# DCDC_stepdown.net
KiCad netlist of a schematic drawn in Altium Designer
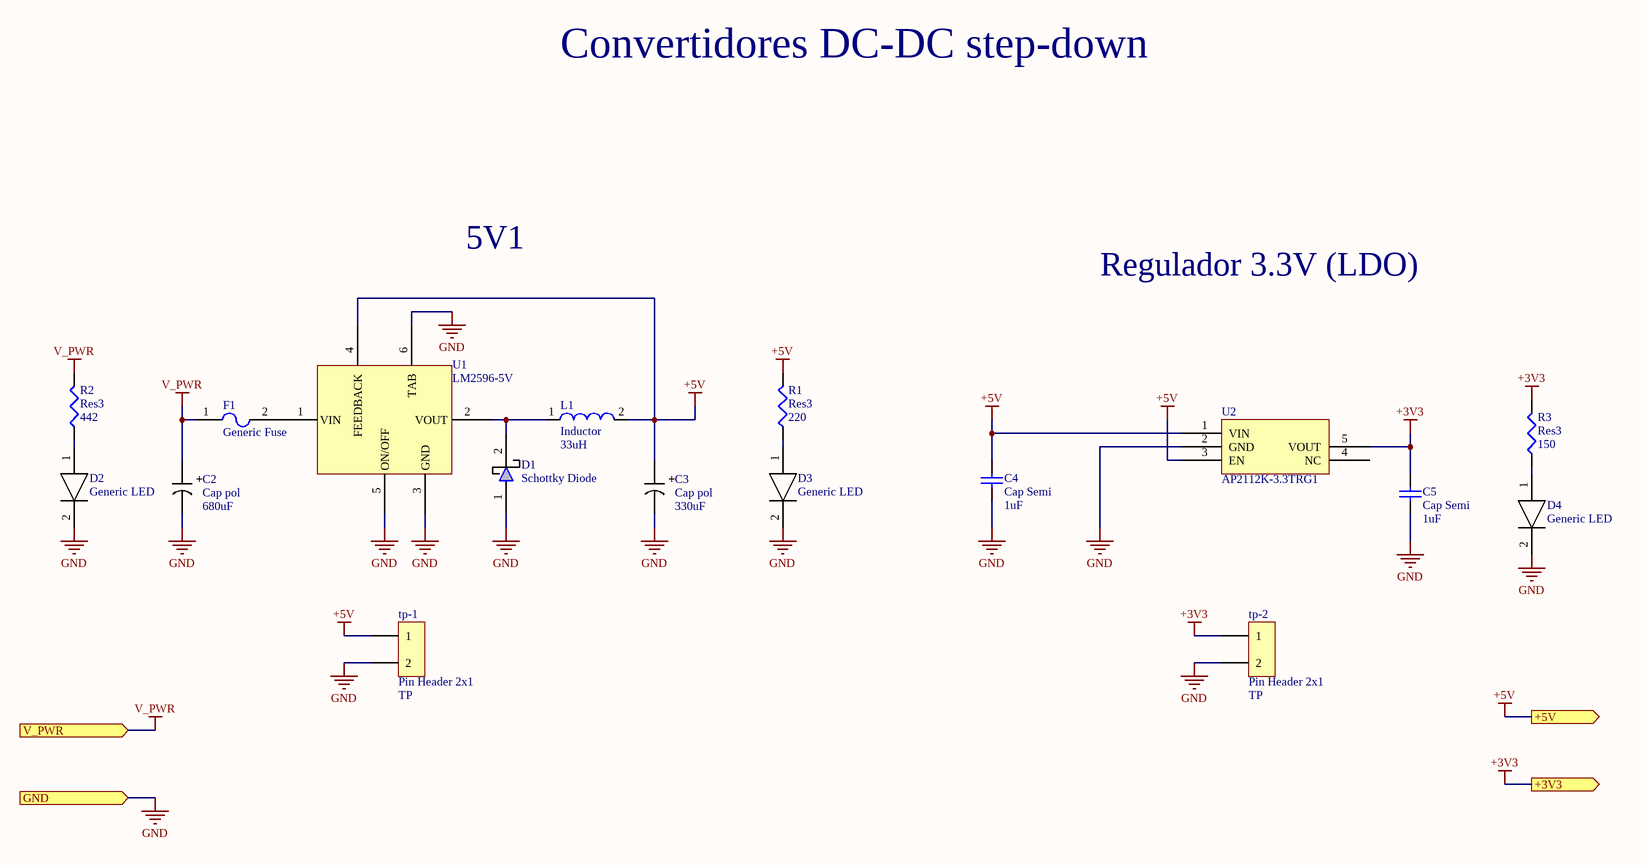
[diagram p0: DCDC_stepdown.SchDoc]

(export (version "E")
  (design (tool "Eeschema 10.0.6"))
  (components
    (comp (ref "C2")
      (value "Cap pol")
      (footprint "CAP_SMD_Electrolytic_10x10")
      (description "Electrolytic Aluminium Capacitor")
      (fields
        (field (name "MANUFACTURER") "PANASONIC")
        (field (name "MANUFACTURER PART NUMBER") "EEEFK1V681AQ")
        (field (name "ALTIUM_VALUE") "680uF")
      )
      (libsource (lib "IoWLabs") (part "Cap pol"))
    )
    (comp (ref "C3")
      (value "Cap pol")
      (footprint "CAP_SMD_Electrolytic_10x10")
      (description "Electrolytic Aluminium Capacitor")
      (fields
        (field (name "MANUFACTURER") "PANASONIC")
        (field (name "MANUFACTURER PART NUMBER") "EEE1VA331UAP")
        (field (name "ALTIUM_VALUE") "330uF")
      )
      (libsource (lib "IoWLabs") (part "Cap pol"))
    )
    (comp (ref "C4")
      (value "Cap Semi")
      (footprint "1608[0603]")
      (description "Capacitor (Semiconductor SIM Model)")
      (fields
        (field (name "ALTIUM_VALUE") "1uF")
        (field (name "MANUFACTURER") "Samsung Electro-Mechanics")
        (field (name "MANUFACTURER PART NUMBER") "CL10B105KO8NNNC")
        (field (name "PUBLISHER") "Altium Limited")
      )
      (libsource (lib "Miscellaneous Devices") (part "Cap Semi"))
    )
    (comp (ref "C5")
      (value "Cap Semi")
      (footprint "1608[0603]")
      (description "Capacitor (Semiconductor SIM Model)")
      (fields
        (field (name "ALTIUM_VALUE") "1uF")
        (field (name "MANUFACTURER") "Samsung Electro-Mechanics")
        (field (name "MANUFACTURER PART NUMBER") "CL10B105KO8NNNC")
        (field (name "PUBLISHER") "Altium Limited")
      )
      (libsource (lib "Miscellaneous Devices") (part "Cap Semi"))
    )
    (comp (ref "D1")
      (value "Schottky Diode")
      (footprint "SMB_L4.6-W3.6-LS5.3-RD")
      (description "Schottky Diodes")
      (fields
        (field (name "MANUFACTURER") "MCC(Micro Commercial Components)")
        (field (name "MANUFACTURER PART NUMBER") "SK32B-LTP")
      )
      (libsource (lib "IoWLabs") (part "Schottky Diode"))
    )
    (comp (ref "D2")
      (value "Generic LED")
      (footprint "LED0603")
      (description "Green 520~535nm 0603 Light Emitting Diodes (LED) ROHS")
      (libsource (lib "IoWLabs") (part "LED"))
    )
    (comp (ref "D3")
      (value "Generic LED")
      (footprint "LED0603")
      (description "Green 520~535nm 0603 Light Emitting Diodes (LED) ROHS")
      (libsource (lib "IoWLabs") (part "LED"))
    )
    (comp (ref "D4")
      (value "Generic LED")
      (footprint "LED0603")
      (description "Green 520~535nm 0603 Light Emitting Diodes (LED) ROHS")
      (libsource (lib "IoWLabs") (part "LED"))
    )
    (comp (ref "F1")
      (value "Generic Fuse")
      (footprint "F1206")
      (description "SMD Fuse")
      (fields (field (name "MANUFACTURER") "AEM") (field (name "MANUFACTURER PART NUMBER") "F1206VH4500TM"))
      (libsource (lib "IoWLabs") (part "FUSE"))
    )
    (comp (ref "L1")
      (value "Inductor")
      (footprint "IND-SMD_L12.5-W12.5_SMDRS1275")
      (description "Inductor SMD")
      (fields
        (field (name "MANUFACTURER") "GLE")
        (field (name "MANUFACTURER PART NUMBER") "GCRH127M-330MC")
        (field (name "ALTIUM_VALUE") "33uH")
      )
      (libsource (lib "IoWLabs") (part "Inductor"))
    )
    (comp (ref "R1")
      (value "Res3")
      (footprint "J1-0603")
      (description "±1% ±100ppm/℃ 0.1W 220Ω 0603 Chip Resistor - Surface Mount ROHS")
      (fields
        (field (name "ALTIUM_VALUE") "220")
        (field (name "MANUFACTURER PART NUMBER") "AC0603FR-07442RL")
        (field (name "MANUFACTURER") "YAGEO")
        (field (name "PUBLISHER") "Altium Limited")
      )
      (libsource (lib "Miscellaneous Devices") (part "Res3"))
    )
    (comp (ref "R2")
      (value "Res3")
      (footprint "J1-0603")
      (description "Resistor")
      (fields
        (field (name "ALTIUM_VALUE") "442")
        (field (name "MANUFACTURER PART NUMBER") "AC0603FR-07442RL")
        (field (name "MANUFACTURER") "YAGEO")
        (field (name "PUBLISHER") "Altium Limited")
      )
      (libsource (lib "Miscellaneous Devices") (part "Res3"))
    )
    (comp (ref "R3")
      (value "Res3")
      (footprint "J1-0603")
      (description "Resistor")
      (fields
        (field (name "ALTIUM_VALUE") "150")
        (field (name "MANUFACTURER PART NUMBER") "AC0603FR-07442RL")
        (field (name "MANUFACTURER") "YAGEO")
        (field (name "PUBLISHER") "Altium Limited")
      )
      (libsource (lib "Miscellaneous Devices") (part "Res3"))
    )
    (comp (ref "tp-1")
      (value "Pin Header 2x1")
      (footprint "HDR-TH_P2.54-H-M_A2541WV-2P")
      (description "Pin Header 2pos, 1 row, 2.54 pitch")
      (fields
        (field (name "MANUFACTURER") "CJT(Changjiang Connectors)")
        (field (name "MANUFACTURER PART NUMBER") "A2541WV-2P")
      )
      (libsource (lib "IoWLabsConnectors") (part "Header - 2x1c"))
    )
    (comp (ref "tp-2")
      (value "Pin Header 2x1")
      (footprint "HDR-TH_P2.54-H-M_A2541WV-2P")
      (description "Pin Header 2pos, 1 row, 2.54 pitch")
      (fields
        (field (name "MANUFACTURER") "CJT(Changjiang Connectors)")
        (field (name "MANUFACTURER PART NUMBER") "A2541WV-2P")
      )
      (libsource (lib "IoWLabsConnectors") (part "Header - 2x1c"))
    )
    (comp (ref "U1")
      (value "LM2596-5V")
      (footprint "TO-263-5")
      (description "Step-Down Positive Fixed 1 3A 150kHz TO-263-5 DC-DC Converters RoHS")
      (fields
        (field (name "MANUFACTURER") "HTC Korea TAEJIN Tech")
        (field (name "MANUFACTURER PART NUMBER") "LM2596R-5.0")
      )
      (libsource (lib "IoWLabs") (part "LM2596-5V"))
    )
    (comp (ref "U2")
      (value "AP2112K-3.3TRG1")
      (footprint "SOT25-5")
      (description "6V 400mV @ 600mA Fixed 3.3V SOT-25 Linear Voltage Regulators (LDO) ROHS")
      (fields (field (name "MANUFACTURER") "DIODES"))
      (libsource (lib "IoWLabs") (part "AP2112K-3.3"))
    )
  )
  (nets
    (net (code "1") (name "+3V3") (class "Default")
      (node (ref "C5") (pin "2") (pinfunction "2_2") (pintype "passive"))
      (node (ref "R3") (pin "2") (pinfunction "2_2") (pintype "passive"))
      (node (ref "U2") (pin "5") (pinfunction "VOUT_5") (pintype "passive"))
      (node (ref "tp-2") (pin "1") (pinfunction "1_1") (pintype "passive"))
    )
    (net (code "2") (name "+5V") (class "Default")
      (node (ref "C3") (pin "2") (pinfunction "2_2") (pintype "passive"))
      (node (ref "C4") (pin "2") (pinfunction "2_2") (pintype "passive"))
      (node (ref "L1") (pin "2") (pinfunction "2_2") (pintype "passive"))
      (node (ref "R1") (pin "2") (pinfunction "2_2") (pintype "passive"))
      (node (ref "U1") (pin "4") (pinfunction "FEEDBACK_4") (pintype "passive"))
      (node (ref "U2") (pin "1") (pinfunction "VIN_1") (pintype "passive"))
      (node (ref "U2") (pin "3") (pinfunction "EN_3") (pintype "passive"))
      (node (ref "tp-1") (pin "1") (pinfunction "1_1") (pintype "passive"))
    )
    (net (code "3") (name "GND") (class "Default")
      (node (ref "C2") (pin "1") (pinfunction "1_1") (pintype "passive"))
      (node (ref "C3") (pin "1") (pinfunction "1_1") (pintype "passive"))
      (node (ref "C4") (pin "1") (pinfunction "1_1") (pintype "passive"))
      (node (ref "C5") (pin "1") (pinfunction "1_1") (pintype "passive"))
      (node (ref "D1") (pin "1") (pinfunction "+_1") (pintype "passive"))
      (node (ref "D2") (pin "2") (pinfunction "2_2") (pintype "passive"))
      (node (ref "D3") (pin "2") (pinfunction "2_2") (pintype "passive"))
      (node (ref "D4") (pin "2") (pinfunction "2_2") (pintype "passive"))
      (node (ref "U1") (pin "3") (pinfunction "GND_3") (pintype "passive"))
      (node (ref "U1") (pin "5") (pinfunction "ON/OFF_5") (pintype "passive"))
      (node (ref "U1") (pin "6") (pinfunction "TAB_6") (pintype "passive"))
      (node (ref "U2") (pin "2") (pinfunction "GND_2") (pintype "passive"))
      (node (ref "tp-1") (pin "2") (pinfunction "2_2") (pintype "passive"))
      (node (ref "tp-2") (pin "2") (pinfunction "2_2") (pintype "passive"))
    )
    (net (code "4") (name "Net-(D1--)") (class "Default")
      (node (ref "D1") (pin "2") (pinfunction "-_2") (pintype "passive"))
      (node (ref "L1") (pin "1") (pinfunction "1_1") (pintype "passive"))
      (node (ref "U1") (pin "2") (pinfunction "VOUT_2") (pintype "passive"))
    )
    (net (code "5") (name "Net-(D2-Pad1)") (class "Default")
      (node (ref "D2") (pin "1") (pinfunction "1_1") (pintype "passive"))
      (node (ref "R2") (pin "1") (pinfunction "1_1") (pintype "passive"))
    )
    (net (code "6") (name "Net-(D3-Pad1)") (class "Default")
      (node (ref "D3") (pin "1") (pinfunction "1_1") (pintype "passive"))
      (node (ref "R1") (pin "1") (pinfunction "1_1") (pintype "passive"))
    )
    (net (code "7") (name "Net-(D4-Pad1)") (class "Default")
      (node (ref "D4") (pin "1") (pinfunction "1_1") (pintype "passive"))
      (node (ref "R3") (pin "1") (pinfunction "1_1") (pintype "passive"))
    )
    (net (code "8") (name "Net-(U1-VIN)") (class "Default")
      (node (ref "F1") (pin "2") (pinfunction "2_2") (pintype "passive"))
      (node (ref "U1") (pin "1") (pinfunction "VIN_1") (pintype "passive"))
    )
    (net (code "9") (name "V_PWR") (class "Default")
      (node (ref "C2") (pin "2") (pinfunction "2_2") (pintype "passive"))
      (node (ref "F1") (pin "1") (pinfunction "1_1") (pintype "passive"))
      (node (ref "R2") (pin "2") (pinfunction "2_2") (pintype "passive"))
    )
    (net (code "10") (name "unconnected-(U2-NC-Pad4)") (class "Default")
      (node (ref "U2") (pin "4") (pinfunction "NC_4") (pintype "passive"))
    )
  )
)
